# Rear_right_lamp_v3B.net
KiCad netlist of a schematic drawn in EAGLE
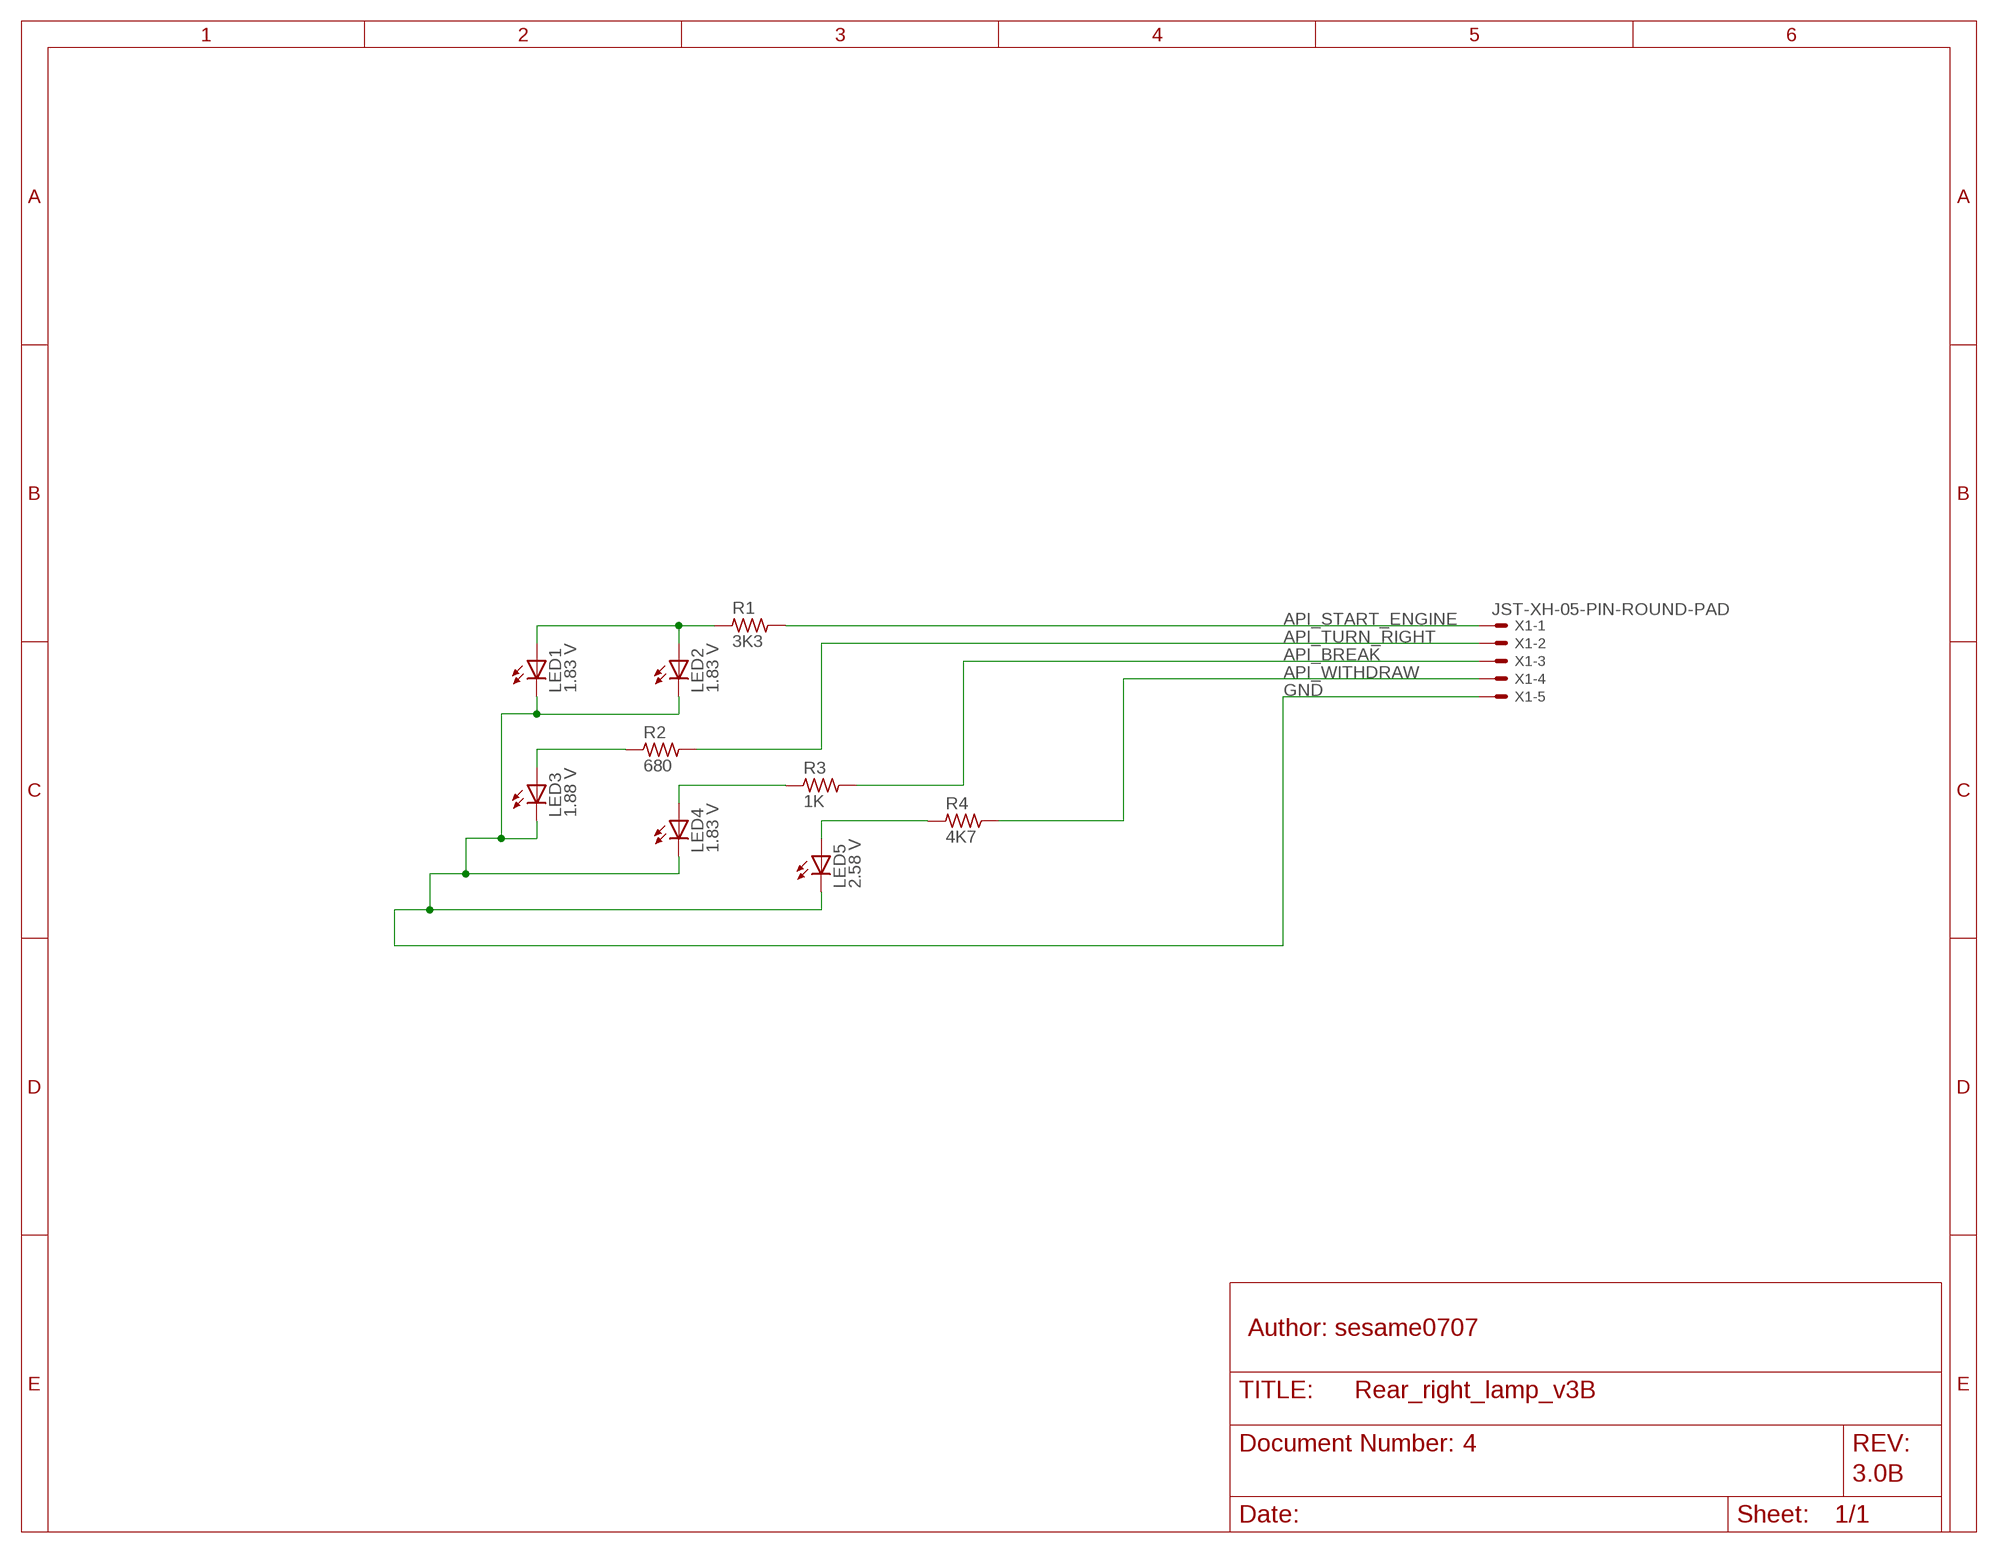
[diagram p0: schematic, sheet 1]

(export (version "E")
  (design (tool "Eeschema 10.0.6"))
  (components
    (comp (ref "LED1")
      (value "1.83 V")
      (footprint "eagle-import:LED5MM")
      (libsource (lib "eagle-import") (part "LED5MM"))
    )
    (comp (ref "LED2")
      (value "1.83 V")
      (footprint "eagle-import:LED5MM")
      (libsource (lib "eagle-import") (part "LED5MM"))
    )
    (comp (ref "LED3")
      (value "1.88 V")
      (footprint "eagle-import:LED5MM")
      (libsource (lib "eagle-import") (part "LED5MM"))
    )
    (comp (ref "LED4")
      (value "1.83 V")
      (footprint "eagle-import:LED5MM")
      (libsource (lib "eagle-import") (part "LED5MM"))
    )
    (comp (ref "LED5")
      (value "2.58 V")
      (footprint "eagle-import:LED5MM")
      (libsource (lib "eagle-import") (part "LED5MM"))
    )
    (comp (ref "R1")
      (value "3K3")
      (footprint "eagle-import:R1206")
      (libsource (lib "eagle-import") (part "R_1206"))
    )
    (comp (ref "R2")
      (value "680")
      (footprint "eagle-import:R1206")
      (libsource (lib "eagle-import") (part "R_1206"))
    )
    (comp (ref "R3")
      (value "1K")
      (footprint "eagle-import:R1206")
      (libsource (lib "eagle-import") (part "R_1206"))
    )
    (comp (ref "R4")
      (value "4K7")
      (footprint "eagle-import:R1206")
      (libsource (lib "eagle-import") (part "R_1206"))
    )
    (comp (ref "X1")
      (value "JST-XH-05-PIN-ROUND-PAD")
      (footprint "eagle-import:JST-XH-05-PACKAGE-ROUND-PAD")
      (libsource (lib "eagle-import") (part "JST-XH-05-PIN-ROUND-PAD"))
    )
  )
  (nets
    (net (code "1") (name "/API_BREAK") (class "Default")
      (node (ref "R3") (pin "2") (pinfunction "2_2") (pintype "passive"))
      (node (ref "X1") (pin "3") (pinfunction "S_3") (pintype "passive"))
    )
    (net (code "2") (name "/API_START_ENGINE") (class "Default")
      (node (ref "LED1") (pin "A") (pinfunction "A_A") (pintype "passive"))
      (node (ref "LED2") (pin "A") (pinfunction "A_A") (pintype "passive"))
      (node (ref "R1") (pin "1") (pinfunction "1_1") (pintype "passive"))
    )
    (net (code "3") (name "/API_TURN_RIGHT") (class "Default")
      (node (ref "R2") (pin "2") (pinfunction "2_2") (pintype "passive"))
      (node (ref "X1") (pin "2") (pinfunction "S_2") (pintype "passive"))
    )
    (net (code "4") (name "/API_WITHDRAW") (class "Default")
      (node (ref "R4") (pin "2") (pinfunction "2_2") (pintype "passive"))
      (node (ref "X1") (pin "4") (pinfunction "S_4") (pintype "passive"))
    )
    (net (code "5") (name "/GND") (class "Default")
      (node (ref "LED1") (pin "K") (pinfunction "C_K") (pintype "passive"))
      (node (ref "LED2") (pin "K") (pinfunction "C_K") (pintype "passive"))
      (node (ref "LED3") (pin "K") (pinfunction "C_K") (pintype "passive"))
      (node (ref "LED4") (pin "K") (pinfunction "C_K") (pintype "passive"))
      (node (ref "LED5") (pin "K") (pinfunction "C_K") (pintype "passive"))
      (node (ref "X1") (pin "5") (pinfunction "S_5") (pintype "passive"))
    )
    (net (code "6") (name "Net-(LED3-PadA)") (class "Default")
      (node (ref "LED3") (pin "A") (pinfunction "A_A") (pintype "passive"))
      (node (ref "R2") (pin "1") (pinfunction "1_1") (pintype "passive"))
    )
    (net (code "7") (name "Net-(LED4-PadA)") (class "Default")
      (node (ref "LED4") (pin "A") (pinfunction "A_A") (pintype "passive"))
      (node (ref "R3") (pin "1") (pinfunction "1_1") (pintype "passive"))
    )
    (net (code "8") (name "Net-(LED5-PadA)") (class "Default")
      (node (ref "LED5") (pin "A") (pinfunction "A_A") (pintype "passive"))
      (node (ref "R4") (pin "1") (pinfunction "1_1") (pintype "passive"))
    )
    (net (code "9") (name "Net-(X1A-S)") (class "Default")
      (node (ref "R1") (pin "2") (pinfunction "2_2") (pintype "passive"))
      (node (ref "X1") (pin "1") (pinfunction "S_1") (pintype "passive"))
    )
  )
)
